# FinalDesign.net
KiCad netlist of a schematic drawn in EAGLE
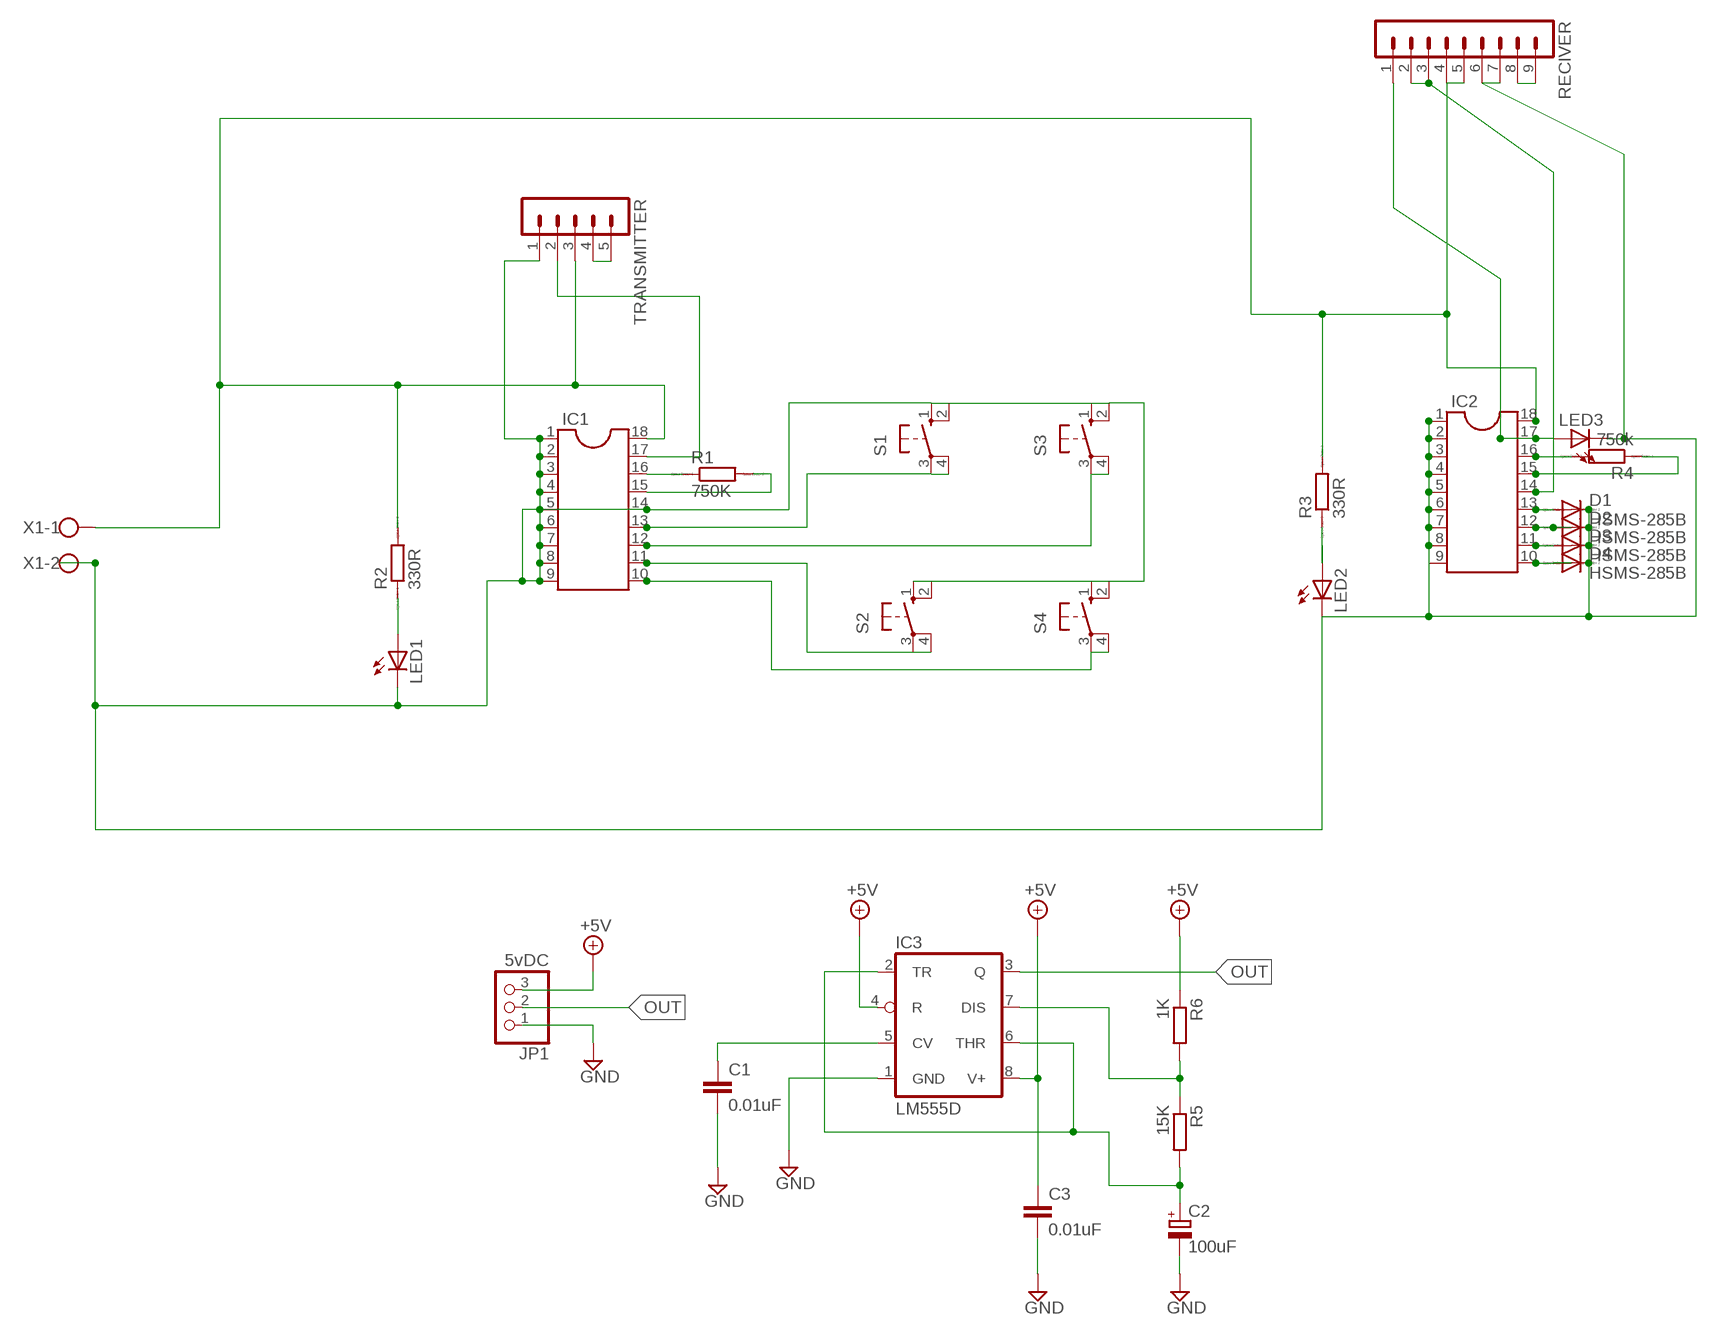
[diagram p0: schematic, sheet 1]

(export (version "E")
  (design (tool "Eeschema 10.0.6"))
  (components
    (comp (ref "C1")
      (value "0.01uF")
      (footprint "eagle-import:C0805")
      (libsource (lib "eagle-import") (part "C-EUC0805"))
    )
    (comp (ref "C2")
      (value "100uF")
      (footprint "eagle-import:E2,5-5")
      (libsource (lib "eagle-import") (part "CPOL-EUE2.5-5"))
    )
    (comp (ref "C3")
      (value "0.01uF")
      (footprint "eagle-import:C0805")
      (libsource (lib "eagle-import") (part "C-EUC0805"))
    )
    (comp (ref "D1")
      (value "HSMS-285B")
      (footprint "eagle-import:SOT323")
      (libsource (lib "eagle-import") (part "HSMS-285B"))
    )
    (comp (ref "D2")
      (value "HSMS-285B")
      (footprint "eagle-import:SOT323")
      (libsource (lib "eagle-import") (part "HSMS-285B"))
    )
    (comp (ref "D3")
      (value "HSMS-285B")
      (footprint "eagle-import:SOT323")
      (libsource (lib "eagle-import") (part "HSMS-285B"))
    )
    (comp (ref "D4")
      (value "HSMS-285B")
      (footprint "eagle-import:SOT323")
      (libsource (lib "eagle-import") (part "HSMS-285B"))
    )
    (comp (ref "IC1")
      (value "DIL18")
      (footprint "eagle-import:DIL18")
      (libsource (lib "eagle-import") (part "DIL18"))
    )
    (comp (ref "IC2")
      (value "DIL18")
      (footprint "eagle-import:DIL18")
      (libsource (lib "eagle-import") (part "DIL18"))
    )
    (comp (ref "IC3")
      (value "LM555D")
      (footprint "eagle-import:SO08")
      (libsource (lib "eagle-import") (part "555DLM"))
    )
    (comp (ref "JP1")
      (value "5vDC")
      (footprint "eagle-import:1X03")
      (libsource (lib "eagle-import") (part "PINHD-1X3"))
    )
    (comp (ref "LED1")
      (value "LED5MM")
      (footprint "eagle-import:LED5MM")
      (libsource (lib "eagle-import") (part "LED5MM"))
    )
    (comp (ref "LED2")
      (value "LED5MM")
      (footprint "eagle-import:LED5MM")
      (libsource (lib "eagle-import") (part "LED5MM"))
    )
    (comp (ref "LED3")
      (value "LED5MM")
      (footprint "eagle-import:LED5MM")
      (libsource (lib "eagle-import") (part "LED5MM"))
    )
    (comp (ref "R1")
      (value "750K")
      (footprint "eagle-import:0207_10")
      (libsource (lib "eagle-import") (part "R0207/10"))
    )
    (comp (ref "R2")
      (value "330R")
      (footprint "eagle-import:0207_10")
      (libsource (lib "eagle-import") (part "R0207/10"))
    )
    (comp (ref "R3")
      (value "330R")
      (footprint "eagle-import:0204_7")
      (libsource (lib "eagle-import") (part "R0204/7"))
    )
    (comp (ref "R4")
      (value "750k")
      (footprint "eagle-import:0204_7")
      (libsource (lib "eagle-import") (part "R0204/7"))
    )
    (comp (ref "R5")
      (value "15K")
      (footprint "eagle-import:M0805")
      (libsource (lib "eagle-import") (part "R-EU_M0805"))
    )
    (comp (ref "R6")
      (value "1K")
      (footprint "eagle-import:M0805")
      (libsource (lib "eagle-import") (part "R-EU_M0805"))
    )
    (comp (ref "RECIVER")
      (value "MA09-1")
      (footprint "eagle-import:MA09-1")
      (libsource (lib "eagle-import") (part "MA09-1"))
    )
    (comp (ref "S1")
      (value "10-XX")
      (footprint "eagle-import:B3F-10XX")
      (fields (field (name "MPN") "B3F-1000"))
      (libsource (lib "eagle-import") (part "10-XX"))
    )
    (comp (ref "S2")
      (value "10-XX")
      (footprint "eagle-import:B3F-10XX")
      (fields (field (name "MPN") "B3F-1000"))
      (libsource (lib "eagle-import") (part "10-XX"))
    )
    (comp (ref "S3")
      (value "10-XX")
      (footprint "eagle-import:B3F-10XX")
      (fields (field (name "MPN") "B3F-1000"))
      (libsource (lib "eagle-import") (part "10-XX"))
    )
    (comp (ref "S4")
      (value "10-XX")
      (footprint "eagle-import:B3F-10XX")
      (fields (field (name "MPN") "B3F-1000"))
      (libsource (lib "eagle-import") (part "10-XX"))
    )
    (comp (ref "TRANSMITTER")
      (value "MA05-1")
      (footprint "eagle-import:MA05-1")
      (libsource (lib "eagle-import") (part "MA05-1"))
    )
    (comp (ref "X1")
      (value "W237-102")
      (footprint "eagle-import:W237-102")
      (fields (field (name "MPN") "237-102"))
      (libsource (lib "eagle-import") (part "W237-102"))
    )
  )
  (nets
    (net (code "1") (name "+5V") (class "Default")
      (node (ref "C3") (pin "1") (pinfunction "1_1") (pintype "passive"))
      (node (ref "IC3") (pin "4") (pinfunction "R_4") (pintype "input"))
      (node (ref "IC3") (pin "8") (pinfunction "V+_8") (pintype "power_in"))
      (node (ref "JP1") (pin "3") (pinfunction "3_3") (pintype "passive"))
      (node (ref "R6") (pin "1") (pinfunction "1_1") (pintype "passive"))
    )
    (net (code "2") (name "GND") (class "Default")
      (node (ref "C1") (pin "2") (pinfunction "2_2") (pintype "passive"))
      (node (ref "C2") (pin "-") (pinfunction "-_-") (pintype "passive"))
      (node (ref "C3") (pin "2") (pinfunction "2_2") (pintype "passive"))
      (node (ref "D1") (pin "3") (pinfunction "C_3") (pintype "passive"))
      (node (ref "D2") (pin "3") (pinfunction "C_3") (pintype "passive"))
      (node (ref "D3") (pin "3") (pinfunction "C_3") (pintype "passive"))
      (node (ref "D4") (pin "3") (pinfunction "C_3") (pintype "passive"))
      (node (ref "IC1") (pin "1") (pinfunction "1_1") (pintype "passive"))
      (node (ref "IC1") (pin "14") (pinfunction "14_14") (pintype "passive"))
      (node (ref "IC1") (pin "2") (pinfunction "2_2") (pintype "passive"))
      (node (ref "IC1") (pin "3") (pinfunction "3_3") (pintype "passive"))
      (node (ref "IC1") (pin "4") (pinfunction "4_4") (pintype "passive"))
      (node (ref "IC1") (pin "5") (pinfunction "5_5") (pintype "passive"))
      (node (ref "IC1") (pin "6") (pinfunction "6_6") (pintype "passive"))
      (node (ref "IC1") (pin "7") (pinfunction "7_7") (pintype "passive"))
      (node (ref "IC1") (pin "8") (pinfunction "8_8") (pintype "passive"))
      (node (ref "IC1") (pin "9") (pinfunction "9_9") (pintype "passive"))
      (node (ref "IC2") (pin "1") (pinfunction "1_1") (pintype "passive"))
      (node (ref "IC2") (pin "2") (pinfunction "2_2") (pintype "passive"))
      (node (ref "IC2") (pin "3") (pinfunction "3_3") (pintype "passive"))
      (node (ref "IC2") (pin "4") (pinfunction "4_4") (pintype "passive"))
      (node (ref "IC2") (pin "5") (pinfunction "5_5") (pintype "passive"))
      (node (ref "IC2") (pin "6") (pinfunction "6_6") (pintype "passive"))
      (node (ref "IC2") (pin "7") (pinfunction "7_7") (pintype "passive"))
      (node (ref "IC2") (pin "8") (pinfunction "8_8") (pintype "passive"))
      (node (ref "IC2") (pin "9") (pinfunction "9_9") (pintype "passive"))
      (node (ref "IC3") (pin "1") (pinfunction "GND_1") (pintype "power_in"))
      (node (ref "JP1") (pin "1") (pinfunction "1_1") (pintype "passive"))
      (node (ref "LED1") (pin "K") (pinfunction "C_K") (pintype "passive"))
      (node (ref "LED2") (pin "K") (pinfunction "C_K") (pintype "passive"))
      (node (ref "LED3") (pin "K") (pinfunction "C_K") (pintype "passive"))
      (node (ref "RECIVER") (pin "6") (pinfunction "6_6") (pintype "passive"))
      (node (ref "RECIVER") (pin "7") (pinfunction "7_7") (pintype "passive"))
      (node (ref "S1") (pin "1") (pinfunction "S_1") (pintype "passive"))
      (node (ref "S1") (pin "2") (pinfunction "S1_2") (pintype "passive"))
      (node (ref "S2") (pin "1") (pinfunction "S_1") (pintype "passive"))
      (node (ref "S2") (pin "2") (pinfunction "S1_2") (pintype "passive"))
      (node (ref "S3") (pin "1") (pinfunction "S_1") (pintype "passive"))
      (node (ref "S3") (pin "2") (pinfunction "S1_2") (pintype "passive"))
      (node (ref "S4") (pin "1") (pinfunction "S_1") (pintype "passive"))
      (node (ref "S4") (pin "2") (pinfunction "S1_2") (pintype "passive"))
      (node (ref "TRANSMITTER") (pin "1") (pinfunction "1_1") (pintype "passive"))
      (node (ref "X1") (pin "2") (pinfunction "KL_2") (pintype "passive"))
    )
    (net (code "3") (name "Net-(D1-A)") (class "Default")
      (node (ref "D1") (pin "1") (pinfunction "A_1") (pintype "passive"))
      (node (ref "IC2") (pin "13") (pinfunction "13_13") (pintype "passive"))
    )
    (net (code "4") (name "Net-(D2-A)") (class "Default")
      (node (ref "D2") (pin "1") (pinfunction "A_1") (pintype "passive"))
      (node (ref "IC2") (pin "12") (pinfunction "12_12") (pintype "passive"))
    )
    (net (code "5") (name "Net-(D3-A)") (class "Default")
      (node (ref "D3") (pin "1") (pinfunction "A_1") (pintype "passive"))
      (node (ref "IC2") (pin "11") (pinfunction "11_11") (pintype "passive"))
    )
    (net (code "6") (name "Net-(D4-A)") (class "Default")
      (node (ref "D4") (pin "1") (pinfunction "A_1") (pintype "passive"))
      (node (ref "IC2") (pin "10") (pinfunction "10_10") (pintype "passive"))
    )
    (net (code "7") (name "Net-(IC1-Pad15)") (class "Default")
      (node (ref "IC1") (pin "15") (pinfunction "15_15") (pintype "passive"))
      (node (ref "R1") (pin "2") (pinfunction "2_2") (pintype "passive"))
    )
    (net (code "8") (name "Net-(IC1-Pad16)") (class "Default")
      (node (ref "IC1") (pin "16") (pinfunction "16_16") (pintype "passive"))
      (node (ref "R1") (pin "1") (pinfunction "1_1") (pintype "passive"))
    )
    (net (code "9") (name "Net-(IC1-Pad17)") (class "Default")
      (node (ref "IC1") (pin "17") (pinfunction "17_17") (pintype "passive"))
      (node (ref "TRANSMITTER") (pin "2") (pinfunction "2_2") (pintype "passive"))
    )
    (net (code "10") (name "Net-(IC2-Pad14)") (class "Default")
      (node (ref "IC2") (pin "14") (pinfunction "14_14") (pintype "passive"))
      (node (ref "RECIVER") (pin "2") (pinfunction "2_2") (pintype "passive"))
      (node (ref "RECIVER") (pin "3") (pinfunction "3_3") (pintype "passive"))
    )
    (net (code "11") (name "Net-(IC2-Pad15)") (class "Default")
      (node (ref "IC2") (pin "15") (pinfunction "15_15") (pintype "passive"))
      (node (ref "R4") (pin "1") (pinfunction "1_1") (pintype "passive"))
    )
    (net (code "12") (name "Net-(IC2-Pad16)") (class "Default")
      (node (ref "IC2") (pin "16") (pinfunction "16_16") (pintype "passive"))
      (node (ref "R4") (pin "2") (pinfunction "2_2") (pintype "passive"))
    )
    (net (code "13") (name "Net-(IC2-Pad17)") (class "Default")
      (node (ref "IC2") (pin "17") (pinfunction "17_17") (pintype "passive"))
      (node (ref "LED3") (pin "A") (pinfunction "A_A") (pintype "passive"))
      (node (ref "RECIVER") (pin "1") (pinfunction "1_1") (pintype "passive"))
    )
    (net (code "14") (name "Net-(IC3-CV)") (class "Default")
      (node (ref "C1") (pin "1") (pinfunction "1_1") (pintype "passive"))
      (node (ref "IC3") (pin "5") (pinfunction "CV_5") (pintype "input"))
    )
    (net (code "15") (name "Net-(IC3-DIS)") (class "Default")
      (node (ref "IC3") (pin "7") (pinfunction "DIS_7") (pintype "input"))
      (node (ref "R5") (pin "1") (pinfunction "1_1") (pintype "passive"))
      (node (ref "R6") (pin "2") (pinfunction "2_2") (pintype "passive"))
    )
    (net (code "16") (name "Net-(IC3-THR)") (class "Default")
      (node (ref "C2") (pin "+") (pinfunction "+_+") (pintype "passive"))
      (node (ref "IC3") (pin "2") (pinfunction "TR_2") (pintype "input"))
      (node (ref "IC3") (pin "6") (pinfunction "THR_6") (pintype "input"))
      (node (ref "R5") (pin "2") (pinfunction "2_2") (pintype "passive"))
    )
    (net (code "17") (name "Net-(LED1-PadA)") (class "Default")
      (node (ref "LED1") (pin "A") (pinfunction "A_A") (pintype "passive"))
      (node (ref "R2") (pin "1") (pinfunction "1_1") (pintype "passive"))
    )
    (net (code "18") (name "Net-(LED2-PadA)") (class "Default")
      (node (ref "LED2") (pin "A") (pinfunction "A_A") (pintype "passive"))
      (node (ref "R3") (pin "1") (pinfunction "1_1") (pintype "passive"))
    )
    (net (code "19") (name "Net-(RECIVER-Pad8)") (class "Default")
      (node (ref "RECIVER") (pin "8") (pinfunction "8_8") (pintype "passive"))
      (node (ref "RECIVER") (pin "9") (pinfunction "9_9") (pintype "passive"))
    )
    (net (code "20") (name "Net-(S1-P)") (class "Default")
      (node (ref "IC1") (pin "13") (pinfunction "13_13") (pintype "passive"))
      (node (ref "S1") (pin "3") (pinfunction "P_3") (pintype "passive"))
      (node (ref "S1") (pin "4") (pinfunction "P1_4") (pintype "passive"))
    )
    (net (code "21") (name "Net-(S2-P)") (class "Default")
      (node (ref "IC1") (pin "11") (pinfunction "11_11") (pintype "passive"))
      (node (ref "S2") (pin "3") (pinfunction "P_3") (pintype "passive"))
      (node (ref "S2") (pin "4") (pinfunction "P1_4") (pintype "passive"))
    )
    (net (code "22") (name "Net-(S3-P)") (class "Default")
      (node (ref "IC1") (pin "12") (pinfunction "12_12") (pintype "passive"))
      (node (ref "S3") (pin "3") (pinfunction "P_3") (pintype "passive"))
      (node (ref "S3") (pin "4") (pinfunction "P1_4") (pintype "passive"))
    )
    (net (code "23") (name "Net-(S4-P)") (class "Default")
      (node (ref "IC1") (pin "10") (pinfunction "10_10") (pintype "passive"))
      (node (ref "S4") (pin "3") (pinfunction "P_3") (pintype "passive"))
      (node (ref "S4") (pin "4") (pinfunction "P1_4") (pintype "passive"))
    )
    (net (code "24") (name "Net-(TRANSMITTER-Pad4)") (class "Default")
      (node (ref "TRANSMITTER") (pin "4") (pinfunction "4_4") (pintype "passive"))
      (node (ref "TRANSMITTER") (pin "5") (pinfunction "5_5") (pintype "passive"))
    )
    (net (code "25") (name "Net-(X1A-KL)") (class "Default")
      (node (ref "IC1") (pin "18") (pinfunction "18_18") (pintype "passive"))
      (node (ref "IC2") (pin "18") (pinfunction "18_18") (pintype "passive"))
      (node (ref "R2") (pin "2") (pinfunction "2_2") (pintype "passive"))
      (node (ref "R3") (pin "2") (pinfunction "2_2") (pintype "passive"))
      (node (ref "RECIVER") (pin "4") (pinfunction "4_4") (pintype "passive"))
      (node (ref "RECIVER") (pin "5") (pinfunction "5_5") (pintype "passive"))
      (node (ref "TRANSMITTER") (pin "3") (pinfunction "3_3") (pintype "passive"))
      (node (ref "X1") (pin "1") (pinfunction "KL_1") (pintype "passive"))
    )
    (net (code "26") (name "OUT") (class "Default")
      (node (ref "IC3") (pin "3") (pinfunction "Q_3") (pintype "output"))
      (node (ref "JP1") (pin "2") (pinfunction "2_2") (pintype "passive"))
    )
  )
)
